# AUDIO.net
KiCad netlist of a schematic drawn in Altium Designer
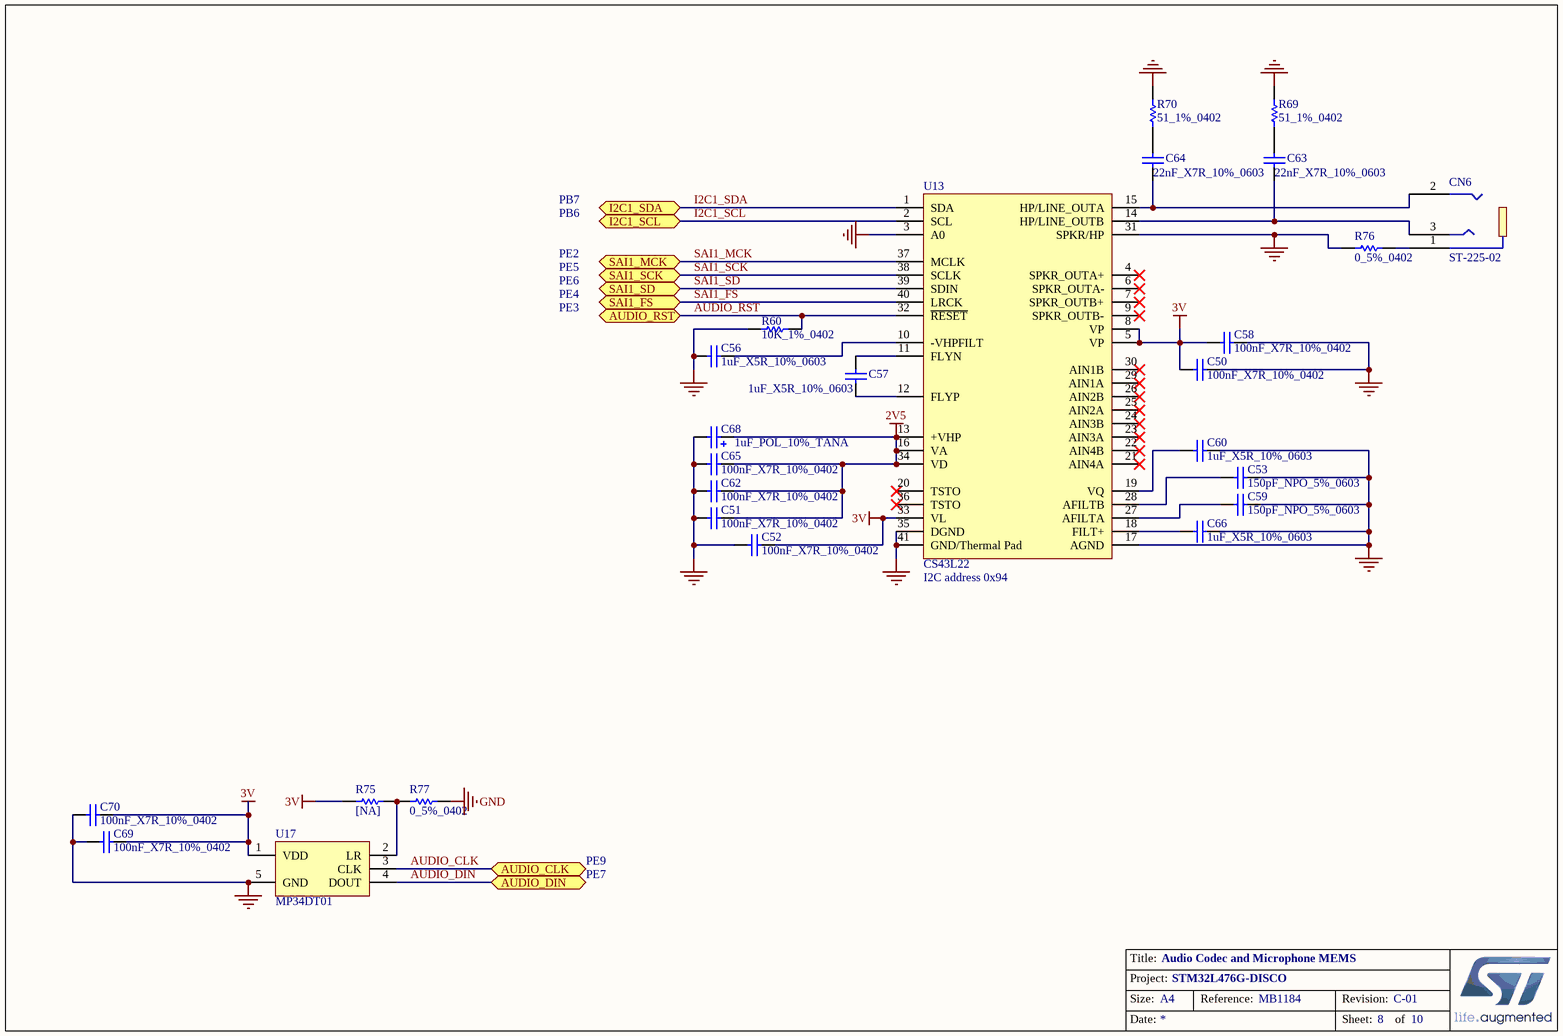
[diagram p0: AUDIO.SchDoc]

(export (version "E")
  (design (tool "Eeschema 10.0.6"))
  (components
    (comp (ref "C50")
      (value "100nF_X7R_10%_0402")
      (footprint "0402C")
      (description "Capacitor,100nF,16V,X7R,10%,0402,YAGEO")
      (libsource (lib "MCD_TOOLS") (part "Cap_100nF_X7R_10%_0402"))
    )
    (comp (ref "C51")
      (value "100nF_X7R_10%_0402")
      (footprint "0402C")
      (description "Capacitor,100nF,16V,X7R,10%,0402,YAGEO")
      (libsource (lib "MCD_TOOLS") (part "Cap_100nF_X7R_10%_0402"))
    )
    (comp (ref "C52")
      (value "100nF_X7R_10%_0402")
      (footprint "0402C")
      (description "Capacitor,100nF,16V,X7R,10%,0402,YAGEO")
      (libsource (lib "MCD_TOOLS") (part "Cap_100nF_X7R_10%_0402"))
    )
    (comp (ref "C53")
      (value "150pF_NPO_5%_0603")
      (footprint "0603C")
      (description "Capacitor,150pF,50V,NPO,5%,0603,YAGEO")
      (libsource (lib "MCD_TOOLS") (part "Cap_150pF_NPO_5%_0603"))
    )
    (comp (ref "C56")
      (value "1uF_X5R_10%_0603")
      (footprint "0603C")
      (description "Capacitor,1uF,16V,X5R,10%,0603,YAGEO")
      (libsource (lib "MCD_TOOLS") (part "Cap_1uF_X5R_10%_0603"))
    )
    (comp (ref "C57")
      (value "1uF_X5R_10%_0603")
      (footprint "0603C")
      (description "Capacitor,1uF,16V,X5R,10%,0603,YAGEO")
      (libsource (lib "MCD_TOOLS") (part "Cap_1uF_X5R_10%_0603"))
    )
    (comp (ref "C58")
      (value "100nF_X7R_10%_0402")
      (footprint "0402C")
      (description "Capacitor,100nF,16V,X7R,10%,0402,YAGEO")
      (libsource (lib "MCD_TOOLS") (part "Cap_100nF_X7R_10%_0402"))
    )
    (comp (ref "C59")
      (value "150pF_NPO_5%_0603")
      (footprint "0603C")
      (description "Capacitor,150pF,50V,NPO,5%,0603,YAGEO")
      (libsource (lib "MCD_TOOLS") (part "Cap_150pF_NPO_5%_0603"))
    )
    (comp (ref "C60")
      (value "1uF_X5R_10%_0603")
      (footprint "0603C")
      (description "Capacitor,1uF,16V,X5R,10%,0603,YAGEO")
      (libsource (lib "MCD_TOOLS") (part "Cap_1uF_X5R_10%_0603"))
    )
    (comp (ref "C62")
      (value "100nF_X7R_10%_0402")
      (footprint "0402C")
      (description "Capacitor,100nF,16V,X7R,10%,0402,YAGEO")
      (libsource (lib "MCD_TOOLS") (part "Cap_100nF_X7R_10%_0402"))
    )
    (comp (ref "C63")
      (value "22nF_X7R_10%_0603")
      (footprint "0603C")
      (description "Capacitor,22nF,50V,X7R,10%,0603,YAGEO")
      (libsource (lib "MCD_TOOLS") (part "Cap_22nF_X7R_10%_0603"))
    )
    (comp (ref "C64")
      (value "22nF_X7R_10%_0603")
      (footprint "0603C")
      (description "Capacitor,22nF,50V,X7R,10%,0603,YAGEO")
      (libsource (lib "MCD_TOOLS") (part "Cap_22nF_X7R_10%_0603"))
    )
    (comp (ref "C65")
      (value "100nF_X7R_10%_0402")
      (footprint "0402C")
      (description "Capacitor,100nF,16V,X7R,10%,0402,YAGEO")
      (libsource (lib "MCD_TOOLS") (part "Cap_100nF_X7R_10%_0402"))
    )
    (comp (ref "C66")
      (value "1uF_X5R_10%_0603")
      (footprint "0603C")
      (description "Capacitor,1uF,16V,X5R,10%,0603,YAGEO")
      (libsource (lib "MCD_TOOLS") (part "Cap_1uF_X5R_10%_0603"))
    )
    (comp (ref "C68")
      (value "1uF_POL_10%_TANA")
      (footprint "TAN-A")
      (description "Polarized Capacitor,1uF,16V,10%,typeA,AVX")
      (libsource (lib "MCD_TOOLS") (part "Cap_1uF_POL_10%_TANA"))
    )
    (comp (ref "C69")
      (value "100nF_X7R_10%_0402")
      (footprint "0402C")
      (description "Capacitor,100nF,16V,X7R,10%,0402,YAGEO")
      (libsource (lib "MCD_TOOLS") (part "Cap_100nF_X7R_10%_0402"))
    )
    (comp (ref "C70")
      (value "100nF_X7R_10%_0402")
      (footprint "0402C")
      (description "Capacitor,100nF,16V,X7R,10%,0402,YAGEO")
      (libsource (lib "MCD_TOOLS") (part "Cap_100nF_X7R_10%_0402"))
    )
    (comp (ref "CN6")
      (value "ST-225-02")
      (footprint "Jack-ST-225")
      (description "Connector Jack 3.5mm")
      (libsource (lib "MCD_TOOLS") (part "ST-225-02"))
    )
    (comp (ref "R60")
      (value "10K_1%_0402")
      (footprint "0402R")
      (description "Resistor,10K,0402,1%,YAGEO")
      (libsource (lib "MCD_TOOLS") (part "Res_10K_1%_0402"))
    )
    (comp (ref "R69")
      (value "51_1%_0402")
      (footprint "0402R")
      (description "Resistor,51,0402,1%,YAGEO")
      (libsource (lib "MCD_TOOLS") (part "Res_51_1%_0402"))
    )
    (comp (ref "R70")
      (value "51_1%_0402")
      (footprint "0402R")
      (description "Resistor,51,0402,1%,YAGEO")
      (libsource (lib "MCD_TOOLS") (part "Res_51_1%_0402"))
    )
    (comp (ref "R75")
      (value "[NA]")
      (footprint "0402R")
      (description "Resistor,[NA],0402")
      (libsource (lib "MCD_TOOLS") (part "Res_NA_0402"))
    )
    (comp (ref "R76")
      (value "0_5%_0402")
      (footprint "0402R")
      (description "Resistor,0,0402,5%,YAGEO")
      (libsource (lib "MCD_TOOLS") (part "Res_0_5%_0402"))
    )
    (comp (ref "R77")
      (value "0_5%_0402")
      (footprint "0402R")
      (description "Resistor,0,0402,5%,YAGEO")
      (libsource (lib "MCD_TOOLS") (part "Res_0_5%_0402"))
    )
    (comp (ref "U13")
      (value "CS43L22")
      (footprint "QFN40_6x6")
      (description "Low Power, Stereo DAC w/Headphone & Speaker Amps")
      (libsource (lib "MCD_TOOLS") (part "CS43L22"))
    )
    (comp (ref "U17")
      (value "MP34DT01")
      (footprint "HCLGA4_3X4")
      (description "MEMS audio sensor, omnidirectional digital microphone")
      (libsource (lib "MCD_TOOLS") (part "MP34DT01"))
    )
  )
  (nets
    (net (code "1") (name "/AUDIO_CLK") (class "Default")
      (node (ref "U17") (pin "3") (pinfunction "CLK_3") (pintype "passive"))
    )
    (net (code "2") (name "/AUDIO_DIN") (class "Default")
      (node (ref "U17") (pin "4") (pinfunction "DOUT_4") (pintype "passive"))
    )
    (net (code "3") (name "/AUDIO_RST") (class "Default")
      (node (ref "R60") (pin "2") (pinfunction "2_2") (pintype "passive"))
      (node (ref "U13") (pin "32") (pinfunction "~{RESET}_32") (pintype "passive"))
    )
    (net (code "4") (name "/I2C1_SCL") (class "Default")
      (node (ref "U13") (pin "2") (pinfunction "SCL_2") (pintype "passive"))
    )
    (net (code "5") (name "/I2C1_SDA") (class "Default")
      (node (ref "U13") (pin "1") (pinfunction "SDA_1") (pintype "passive"))
    )
    (net (code "6") (name "/SAI1_FS") (class "Default")
      (node (ref "U13") (pin "40") (pinfunction "LRCK_40") (pintype "passive"))
    )
    (net (code "7") (name "/SAI1_MCK") (class "Default")
      (node (ref "U13") (pin "37") (pinfunction "MCLK_37") (pintype "passive"))
    )
    (net (code "8") (name "/SAI1_SCK") (class "Default")
      (node (ref "U13") (pin "38") (pinfunction "SCLK_38") (pintype "passive"))
    )
    (net (code "9") (name "/SAI1_SD") (class "Default")
      (node (ref "U13") (pin "39") (pinfunction "SDIN_39") (pintype "passive"))
    )
    (net (code "10") (name "2V5") (class "Default")
      (node (ref "C51") (pin "2") (pinfunction "2_2") (pintype "passive"))
      (node (ref "C62") (pin "2") (pinfunction "2_2") (pintype "passive"))
      (node (ref "C65") (pin "2") (pinfunction "2_2") (pintype "passive"))
      (node (ref "C68") (pin "1") (pinfunction "1_1") (pintype "passive"))
      (node (ref "U13") (pin "13") (pinfunction "+VHP_13") (pintype "passive"))
      (node (ref "U13") (pin "16") (pinfunction "VA_16") (pintype "passive"))
      (node (ref "U13") (pin "34") (pinfunction "VD_34") (pintype "passive"))
    )
    (net (code "11") (name "3V") (class "Default")
      (node (ref "C50") (pin "1") (pinfunction "1_1") (pintype "passive"))
      (node (ref "C52") (pin "2") (pinfunction "2_2") (pintype "passive"))
      (node (ref "C58") (pin "1") (pinfunction "1_1") (pintype "passive"))
      (node (ref "C69") (pin "2") (pinfunction "2_2") (pintype "passive"))
      (node (ref "C70") (pin "2") (pinfunction "2_2") (pintype "passive"))
      (node (ref "R75") (pin "2") (pinfunction "2_2") (pintype "passive"))
      (node (ref "U13") (pin "33") (pinfunction "VL_33") (pintype "passive"))
      (node (ref "U13") (pin "5") (pinfunction "VP_5") (pintype "passive"))
      (node (ref "U13") (pin "8") (pinfunction "VP_8") (pintype "passive"))
      (node (ref "U17") (pin "1") (pinfunction "VDD_1") (pintype "passive"))
    )
    (net (code "12") (name "GND") (class "Default")
      (node (ref "C50") (pin "2") (pinfunction "2_2") (pintype "passive"))
      (node (ref "C51") (pin "1") (pinfunction "1_1") (pintype "passive"))
      (node (ref "C52") (pin "1") (pinfunction "1_1") (pintype "passive"))
      (node (ref "C53") (pin "2") (pinfunction "2_2") (pintype "passive"))
      (node (ref "C56") (pin "1") (pinfunction "1_1") (pintype "passive"))
      (node (ref "C58") (pin "2") (pinfunction "2_2") (pintype "passive"))
      (node (ref "C59") (pin "2") (pinfunction "2_2") (pintype "passive"))
      (node (ref "C60") (pin "2") (pinfunction "2_2") (pintype "passive"))
      (node (ref "C62") (pin "1") (pinfunction "1_1") (pintype "passive"))
      (node (ref "C65") (pin "1") (pinfunction "1_1") (pintype "passive"))
      (node (ref "C66") (pin "2") (pinfunction "2_2") (pintype "passive"))
      (node (ref "C68") (pin "2") (pinfunction "2_2") (pintype "passive"))
      (node (ref "C69") (pin "1") (pinfunction "1_1") (pintype "passive"))
      (node (ref "C70") (pin "1") (pinfunction "1_1") (pintype "passive"))
      (node (ref "R60") (pin "1") (pinfunction "1_1") (pintype "passive"))
      (node (ref "R69") (pin "2") (pinfunction "2_2") (pintype "passive"))
      (node (ref "R70") (pin "2") (pinfunction "2_2") (pintype "passive"))
      (node (ref "R76") (pin "1") (pinfunction "1_1") (pintype "passive"))
      (node (ref "R77") (pin "1") (pinfunction "1_1") (pintype "passive"))
      (node (ref "U13") (pin "17") (pinfunction "AGND_17") (pintype "passive"))
      (node (ref "U13") (pin "3") (pinfunction "A0_3") (pintype "passive"))
      (node (ref "U13") (pin "31") (pinfunction "SPKR/HP_31") (pintype "passive"))
      (node (ref "U13") (pin "35") (pinfunction "DGND_35") (pintype "passive"))
      (node (ref "U13") (pin "41") (pinfunction "GND/Thermal_Pad_41") (pintype "passive"))
      (node (ref "U17") (pin "5") (pinfunction "GND_5") (pintype "passive"))
    )
    (net (code "13") (name "Net-(C63-Pad2)") (class "Default")
      (node (ref "C63") (pin "2") (pinfunction "2_2") (pintype "passive"))
      (node (ref "R69") (pin "1") (pinfunction "1_1") (pintype "passive"))
    )
    (net (code "14") (name "Net-(C64-Pad2)") (class "Default")
      (node (ref "C64") (pin "2") (pinfunction "2_2") (pintype "passive"))
      (node (ref "R70") (pin "1") (pinfunction "1_1") (pintype "passive"))
    )
    (net (code "15") (name "Net-(CN6-Pad1)") (class "Default")
      (node (ref "CN6") (pin "1") (pintype "passive"))
      (node (ref "R76") (pin "2") (pinfunction "2_2") (pintype "passive"))
    )
    (net (code "16") (name "Net-(U13--VHPFILT)") (class "Default")
      (node (ref "C56") (pin "2") (pinfunction "2_2") (pintype "passive"))
      (node (ref "U13") (pin "10") (pinfunction "-VHPFILT_10") (pintype "passive"))
    )
    (net (code "17") (name "Net-(U13-AFILTA)") (class "Default")
      (node (ref "C59") (pin "1") (pinfunction "1_1") (pintype "passive"))
      (node (ref "U13") (pin "27") (pinfunction "AFILTA_27") (pintype "passive"))
    )
    (net (code "18") (name "Net-(U13-AFILTB)") (class "Default")
      (node (ref "C53") (pin "1") (pinfunction "1_1") (pintype "passive"))
      (node (ref "U13") (pin "28") (pinfunction "AFILTB_28") (pintype "passive"))
    )
    (net (code "19") (name "Net-(U13-FILT+)") (class "Default")
      (node (ref "C66") (pin "1") (pinfunction "1_1") (pintype "passive"))
      (node (ref "U13") (pin "18") (pinfunction "FILT+_18") (pintype "passive"))
    )
    (net (code "20") (name "Net-(U13-FLYN)") (class "Default")
      (node (ref "C57") (pin "2") (pinfunction "2_2") (pintype "passive"))
      (node (ref "U13") (pin "11") (pinfunction "FLYN_11") (pintype "passive"))
    )
    (net (code "21") (name "Net-(U13-FLYP)") (class "Default")
      (node (ref "C57") (pin "1") (pinfunction "1_1") (pintype "passive"))
      (node (ref "U13") (pin "12") (pinfunction "FLYP_12") (pintype "passive"))
    )
    (net (code "22") (name "Net-(U13-HP{slash}LINE_OUTA)") (class "Default")
      (node (ref "C64") (pin "1") (pinfunction "1_1") (pintype "passive"))
      (node (ref "CN6") (pin "2") (pintype "passive"))
      (node (ref "U13") (pin "15") (pinfunction "HP/LINE_OUTA_15") (pintype "passive"))
    )
    (net (code "23") (name "Net-(U13-HP{slash}LINE_OUTB)") (class "Default")
      (node (ref "C63") (pin "1") (pinfunction "1_1") (pintype "passive"))
      (node (ref "CN6") (pin "3") (pintype "passive"))
      (node (ref "U13") (pin "14") (pinfunction "HP/LINE_OUTB_14") (pintype "passive"))
    )
    (net (code "24") (name "Net-(U13-VQ)") (class "Default")
      (node (ref "C60") (pin "1") (pinfunction "1_1") (pintype "passive"))
      (node (ref "U13") (pin "19") (pinfunction "VQ_19") (pintype "passive"))
    )
    (net (code "25") (name "Net-(U17-LR)") (class "Default")
      (node (ref "R75") (pin "1") (pinfunction "1_1") (pintype "passive"))
      (node (ref "R77") (pin "2") (pinfunction "2_2") (pintype "passive"))
      (node (ref "U17") (pin "2") (pinfunction "LR_2") (pintype "passive"))
    )
    (net (code "26") (name "unconnected-(U13-AIN1A-Pad29)") (class "Default")
      (node (ref "U13") (pin "29") (pinfunction "AIN1A_29") (pintype "passive+no_connect"))
    )
    (net (code "27") (name "unconnected-(U13-AIN1B-Pad30)") (class "Default")
      (node (ref "U13") (pin "30") (pinfunction "AIN1B_30") (pintype "passive+no_connect"))
    )
    (net (code "28") (name "unconnected-(U13-AIN2A-Pad25)") (class "Default")
      (node (ref "U13") (pin "25") (pinfunction "AIN2A_25") (pintype "passive+no_connect"))
    )
    (net (code "29") (name "unconnected-(U13-AIN2B-Pad26)") (class "Default")
      (node (ref "U13") (pin "26") (pinfunction "AIN2B_26") (pintype "passive+no_connect"))
    )
    (net (code "30") (name "unconnected-(U13-AIN3A-Pad23)") (class "Default")
      (node (ref "U13") (pin "23") (pinfunction "AIN3A_23") (pintype "passive+no_connect"))
    )
    (net (code "31") (name "unconnected-(U13-AIN3B-Pad24)") (class "Default")
      (node (ref "U13") (pin "24") (pinfunction "AIN3B_24") (pintype "passive+no_connect"))
    )
    (net (code "32") (name "unconnected-(U13-AIN4A-Pad21)") (class "Default")
      (node (ref "U13") (pin "21") (pinfunction "AIN4A_21") (pintype "passive+no_connect"))
    )
    (net (code "33") (name "unconnected-(U13-AIN4B-Pad22)") (class "Default")
      (node (ref "U13") (pin "22") (pinfunction "AIN4B_22") (pintype "passive+no_connect"))
    )
    (net (code "34") (name "unconnected-(U13-SPKR_OUTA+-Pad4)") (class "Default")
      (node (ref "U13") (pin "4") (pinfunction "SPKR_OUTA+_4") (pintype "passive+no_connect"))
    )
    (net (code "35") (name "unconnected-(U13-SPKR_OUTA--Pad6)") (class "Default")
      (node (ref "U13") (pin "6") (pinfunction "SPKR_OUTA-_6") (pintype "passive+no_connect"))
    )
    (net (code "36") (name "unconnected-(U13-SPKR_OUTB+-Pad7)") (class "Default")
      (node (ref "U13") (pin "7") (pinfunction "SPKR_OUTB+_7") (pintype "passive+no_connect"))
    )
    (net (code "37") (name "unconnected-(U13-SPKR_OUTB--Pad9)") (class "Default")
      (node (ref "U13") (pin "9") (pinfunction "SPKR_OUTB-_9") (pintype "passive+no_connect"))
    )
    (net (code "38") (name "unconnected-(U13-TSTO-Pad20)") (class "Default")
      (node (ref "U13") (pin "20") (pinfunction "TSTO_20") (pintype "passive+no_connect"))
    )
    (net (code "39") (name "unconnected-(U13-TSTO-Pad36)") (class "Default")
      (node (ref "U13") (pin "36") (pinfunction "TSTO_36") (pintype "passive+no_connect"))
    )
  )
)
